# schema_v4_3.net
KiCad netlist of a schematic drawn in EAGLE
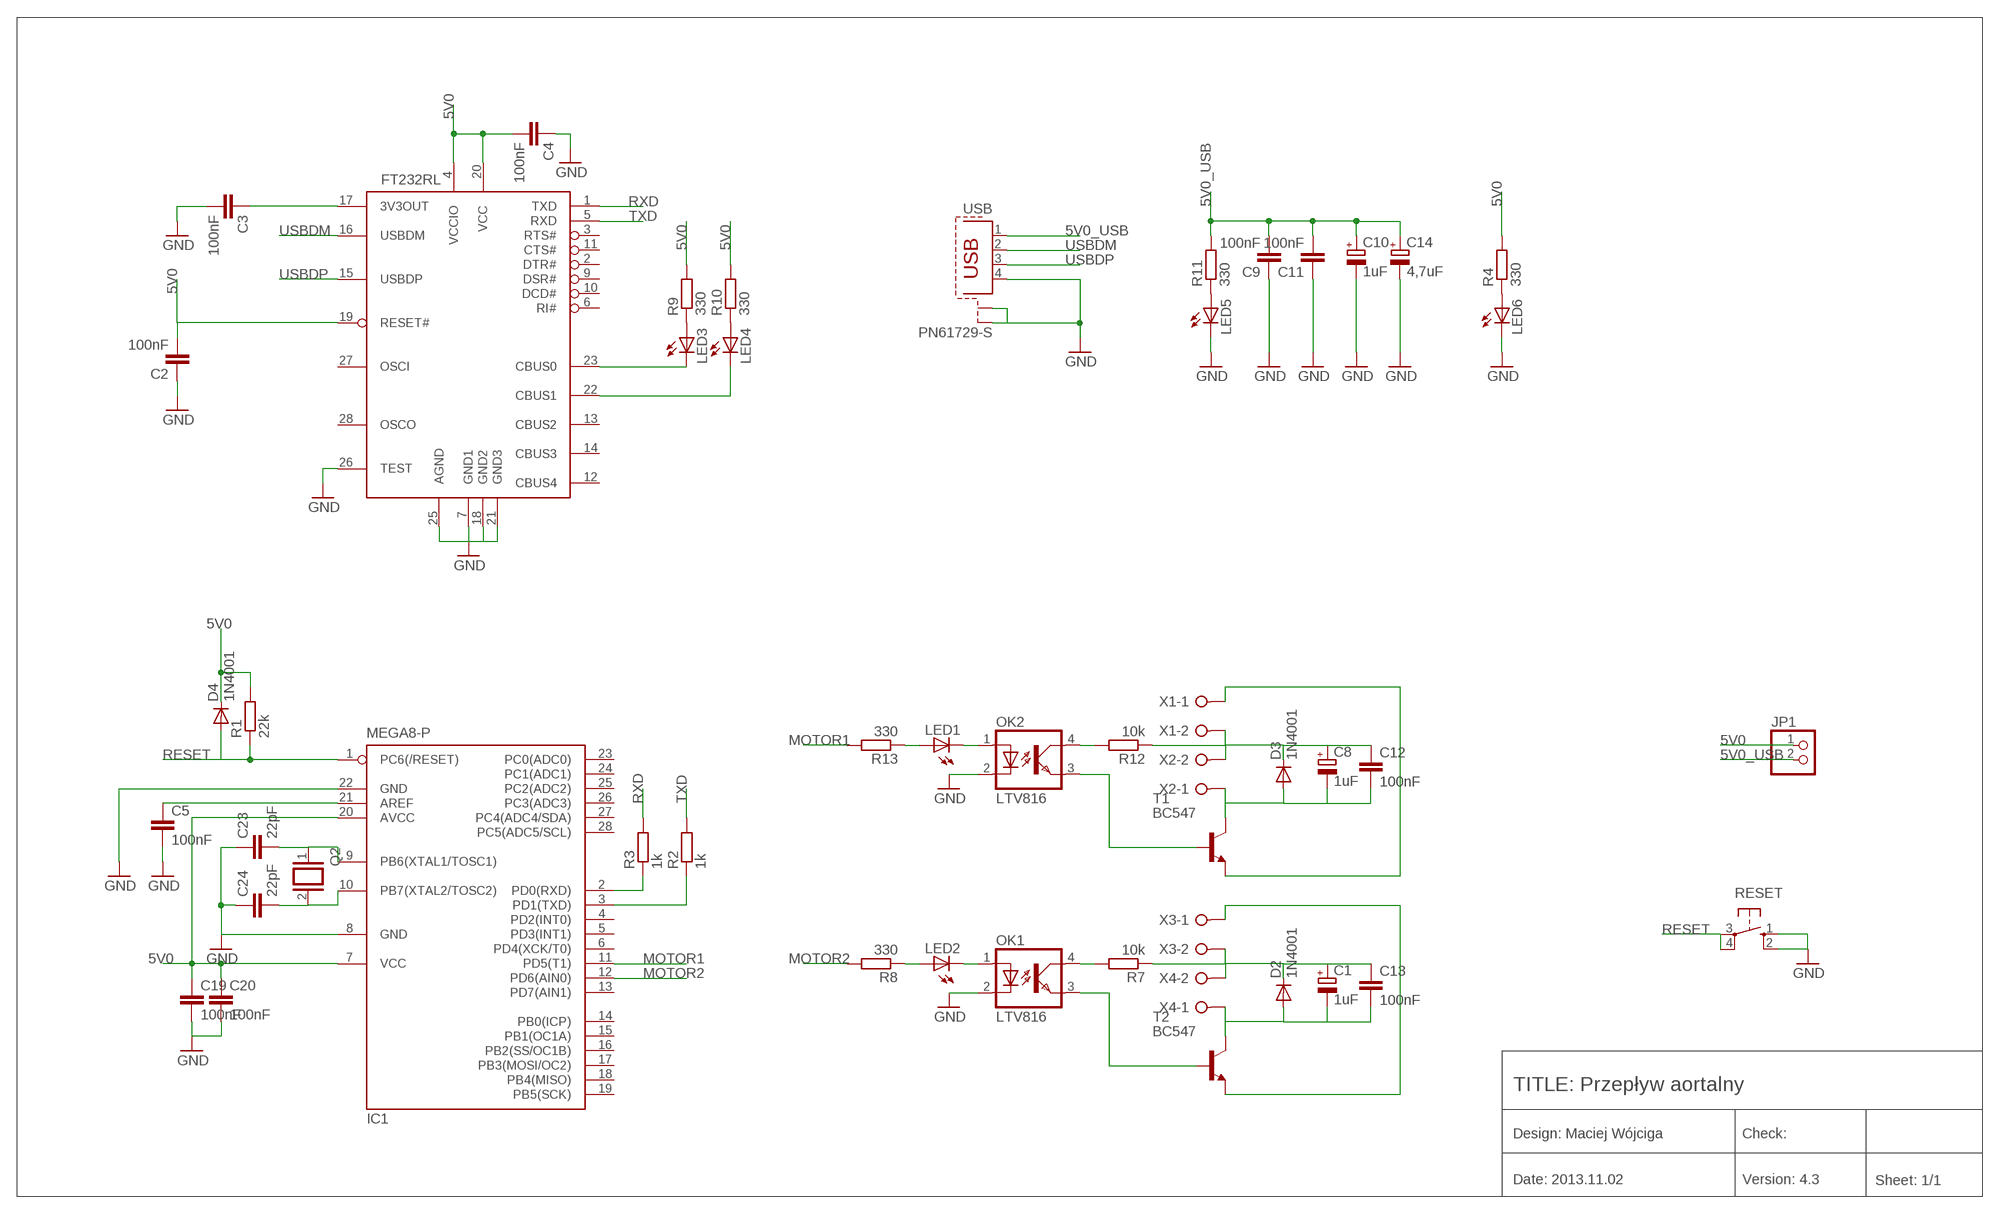
[diagram p0: schematic, sheet 1]

(export (version "E")
  (design (tool "Eeschema 10.0.6"))
  (components
    (comp (ref "C1")
      (value "1uF")
      (footprint "eagle-import:E2,5-5")
      (libsource (lib "eagle-import") (part "CPOL-EUE2.5-5"))
    )
    (comp (ref "C2")
      (value "100nF")
      (footprint "eagle-import:C025-025X050")
      (libsource (lib "eagle-import") (part "C-EU025-025X050"))
    )
    (comp (ref "C3")
      (value "100nF")
      (footprint "eagle-import:C025-025X050")
      (libsource (lib "eagle-import") (part "C-EU025-025X050"))
    )
    (comp (ref "C4")
      (value "100nF")
      (footprint "eagle-import:C025-025X050")
      (libsource (lib "eagle-import") (part "C-EU025-025X050"))
    )
    (comp (ref "C5")
      (value "100nF")
      (footprint "eagle-import:C025-025X050")
      (libsource (lib "eagle-import") (part "C-EU025-025X050"))
    )
    (comp (ref "C8")
      (value "1uF")
      (footprint "eagle-import:E2,5-5")
      (libsource (lib "eagle-import") (part "CPOL-EUE2.5-5"))
    )
    (comp (ref "C9")
      (value "100nF")
      (footprint "eagle-import:C025-025X050")
      (libsource (lib "eagle-import") (part "C-EU025-025X050"))
    )
    (comp (ref "C10")
      (value "1uF")
      (footprint "eagle-import:E2,5-5")
      (libsource (lib "eagle-import") (part "CPOL-EUE2.5-5"))
    )
    (comp (ref "C11")
      (value "100nF")
      (footprint "eagle-import:C025-025X050")
      (libsource (lib "eagle-import") (part "C-EU025-025X050"))
    )
    (comp (ref "C12")
      (value "100nF")
      (footprint "eagle-import:C025-025X050")
      (libsource (lib "eagle-import") (part "C-EU025-025X050"))
    )
    (comp (ref "C13")
      (value "100nF")
      (footprint "eagle-import:C025-025X050")
      (libsource (lib "eagle-import") (part "C-EU025-025X050"))
    )
    (comp (ref "C14")
      (value "4,7uF")
      (footprint "eagle-import:E2,5-5")
      (libsource (lib "eagle-import") (part "CPOL-EUE2.5-5"))
    )
    (comp (ref "C19")
      (value "100nF")
      (footprint "eagle-import:C025-025X050")
      (libsource (lib "eagle-import") (part "C-EU025-025X050"))
    )
    (comp (ref "C20")
      (value "100nF")
      (footprint "eagle-import:C025-025X050")
      (libsource (lib "eagle-import") (part "C-EU025-025X050"))
    )
    (comp (ref "C23")
      (value "22pF")
      (footprint "eagle-import:C025-025X050")
      (libsource (lib "eagle-import") (part "C-EU025-025X050"))
    )
    (comp (ref "C24")
      (value "22pF")
      (footprint "eagle-import:C025-025X050")
      (libsource (lib "eagle-import") (part "C-EU025-025X050"))
    )
    (comp (ref "D2")
      (value "1N4001")
      (footprint "eagle-import:DO41-10")
      (libsource (lib "eagle-import") (part "1N4004"))
    )
    (comp (ref "D3")
      (value "1N4001")
      (footprint "eagle-import:DO41-10")
      (libsource (lib "eagle-import") (part "1N4004"))
    )
    (comp (ref "D4")
      (value "1N4001")
      (footprint "eagle-import:DO41-10")
      (libsource (lib "eagle-import") (part "1N4004"))
    )
    (comp (ref "FT232RL")
      (value "FT232RL")
      (footprint "eagle-import:SSOP28DB")
      (libsource (lib "eagle-import") (part "FT232RL"))
    )
    (comp (ref "IC1")
      (value "MEGA8-P")
      (footprint "eagle-import:DIL28-3")
      (libsource (lib "eagle-import") (part "MEGA8-P"))
    )
    (comp (ref "JP1")
      (value "PINHD-1X2")
      (footprint "eagle-import:1X02")
      (libsource (lib "eagle-import") (part "PINHD-1X2"))
    )
    (comp (ref "LED1")
      (value "LED3MM")
      (footprint "eagle-import:LED3MM")
      (libsource (lib "eagle-import") (part "LED3MM"))
    )
    (comp (ref "LED2")
      (value "LED3MM")
      (footprint "eagle-import:LED3MM")
      (libsource (lib "eagle-import") (part "LED3MM"))
    )
    (comp (ref "LED3")
      (value "LED3MM")
      (footprint "eagle-import:LED3MM")
      (libsource (lib "eagle-import") (part "LED3MM"))
    )
    (comp (ref "LED4")
      (value "LED3MM")
      (footprint "eagle-import:LED3MM")
      (libsource (lib "eagle-import") (part "LED3MM"))
    )
    (comp (ref "LED5")
      (value "LED3MM")
      (footprint "eagle-import:LED3MM")
      (libsource (lib "eagle-import") (part "LED3MM"))
    )
    (comp (ref "LED6")
      (value "LED3MM")
      (footprint "eagle-import:LED3MM")
      (libsource (lib "eagle-import") (part "LED3MM"))
    )
    (comp (ref "OK1")
      (value "LTV816")
      (footprint "eagle-import:DIL04")
      (libsource (lib "eagle-import") (part "LTV816"))
    )
    (comp (ref "OK2")
      (value "LTV816")
      (footprint "eagle-import:DIL04")
      (libsource (lib "eagle-import") (part "LTV816"))
    )
    (comp (ref "Q2")
      (value "XTAL/S")
      (footprint "eagle-import:QS")
      (libsource (lib "eagle-import") (part "XTAL/S"))
    )
    (comp (ref "R1")
      (value "22k")
      (footprint "eagle-import:0207_10")
      (libsource (lib "eagle-import") (part "R-EU_0207/10"))
    )
    (comp (ref "R2")
      (value "1k")
      (footprint "eagle-import:0207_10")
      (libsource (lib "eagle-import") (part "R-EU_0207/10"))
    )
    (comp (ref "R3")
      (value "1k")
      (footprint "eagle-import:0207_10")
      (libsource (lib "eagle-import") (part "R-EU_0207/10"))
    )
    (comp (ref "R4")
      (value "330")
      (footprint "eagle-import:0207_10")
      (libsource (lib "eagle-import") (part "R-EU_0207/10"))
    )
    (comp (ref "R7")
      (value "10k")
      (footprint "eagle-import:0207_10")
      (libsource (lib "eagle-import") (part "R-EU_0207/10"))
    )
    (comp (ref "R8")
      (value "330")
      (footprint "eagle-import:0207_10")
      (libsource (lib "eagle-import") (part "R-EU_0207/10"))
    )
    (comp (ref "R9")
      (value "330")
      (footprint "eagle-import:0207_10")
      (libsource (lib "eagle-import") (part "R-EU_0207/10"))
    )
    (comp (ref "R10")
      (value "330")
      (footprint "eagle-import:0207_10")
      (libsource (lib "eagle-import") (part "R-EU_0207/10"))
    )
    (comp (ref "R11")
      (value "330")
      (footprint "eagle-import:0207_10")
      (libsource (lib "eagle-import") (part "R-EU_0207/10"))
    )
    (comp (ref "R12")
      (value "10k")
      (footprint "eagle-import:0207_10")
      (libsource (lib "eagle-import") (part "R-EU_0207/10"))
    )
    (comp (ref "R13")
      (value "330")
      (footprint "eagle-import:0207_10")
      (libsource (lib "eagle-import") (part "R-EU_0207/10"))
    )
    (comp (ref "RESET")
      (value "10-XX")
      (footprint "eagle-import:B3F-10XX")
      (fields (field (name "MPN") "B3F-1000"))
      (libsource (lib "eagle-import") (part "10-XX"))
    )
    (comp (ref "T1")
      (value "BC547")
      (footprint "eagle-import:TO92")
      (libsource (lib "eagle-import") (part "BC547"))
    )
    (comp (ref "T2")
      (value "BC547")
      (footprint "eagle-import:TO92")
      (libsource (lib "eagle-import") (part "BC547"))
    )
    (comp (ref "USB")
      (value "PN61729-S")
      (footprint "eagle-import:PN61729-S")
      (fields (field (name "OC_FARNELL") "unknown") (field (name "OC_NEWARK") "unknown"))
      (libsource (lib "eagle-import") (part "PN61729-S"))
    )
    (comp (ref "X1")
      (value "W237-02P")
      (footprint "eagle-import:W237-132")
      (fields (field (name "OC_FARNELL") "unknown") (field (name "OC_NEWARK") "unknown"))
      (libsource (lib "eagle-import") (part "W237-02P"))
    )
    (comp (ref "X2")
      (value "W237-02P")
      (footprint "eagle-import:W237-132")
      (fields (field (name "OC_FARNELL") "unknown") (field (name "OC_NEWARK") "unknown"))
      (libsource (lib "eagle-import") (part "W237-02P"))
    )
    (comp (ref "X3")
      (value "W237-02P")
      (footprint "eagle-import:W237-132")
      (fields (field (name "OC_FARNELL") "unknown") (field (name "OC_NEWARK") "unknown"))
      (libsource (lib "eagle-import") (part "W237-02P"))
    )
    (comp (ref "X4")
      (value "W237-02P")
      (footprint "eagle-import:W237-132")
      (fields (field (name "OC_FARNELL") "unknown") (field (name "OC_NEWARK") "unknown"))
      (libsource (lib "eagle-import") (part "W237-02P"))
    )
  )
  (nets
    (net (code "1") (name "/5V0") (class "Default")
      (node (ref "C19") (pin "1") (pinfunction "1_1") (pintype "passive"))
      (node (ref "C2") (pin "2") (pinfunction "2_2") (pintype "passive"))
      (node (ref "C20") (pin "1") (pinfunction "1_1") (pintype "passive"))
      (node (ref "C4") (pin "2") (pinfunction "2_2") (pintype "passive"))
      (node (ref "D4") (pin "C") (pinfunction "C_C") (pintype "passive"))
      (node (ref "FT232RL") (pin "19") (pinfunction "RESET#_19") (pintype "input"))
      (node (ref "FT232RL") (pin "20") (pinfunction "VCC_20") (pintype "power_in"))
      (node (ref "FT232RL") (pin "4") (pinfunction "VCCIO_4") (pintype "power_in"))
      (node (ref "IC1") (pin "20") (pinfunction "AVCC_20") (pintype "power_in"))
      (node (ref "IC1") (pin "7") (pinfunction "VCC_7") (pintype "power_in"))
      (node (ref "JP1") (pin "1") (pinfunction "1_1") (pintype "passive"))
      (node (ref "R1") (pin "2") (pinfunction "2_2") (pintype "passive"))
      (node (ref "R10") (pin "2") (pinfunction "2_2") (pintype "passive"))
      (node (ref "R4") (pin "2") (pinfunction "2_2") (pintype "passive"))
      (node (ref "R9") (pin "2") (pinfunction "2_2") (pintype "passive"))
    )
    (net (code "2") (name "/5V0_USB") (class "Default")
      (node (ref "C10") (pin "+") (pinfunction "+_+") (pintype "passive"))
      (node (ref "C11") (pin "2") (pinfunction "2_2") (pintype "passive"))
      (node (ref "C14") (pin "+") (pinfunction "+_+") (pintype "passive"))
      (node (ref "C9") (pin "2") (pinfunction "2_2") (pintype "passive"))
      (node (ref "JP1") (pin "2") (pinfunction "2_2") (pintype "passive"))
      (node (ref "R11") (pin "2") (pinfunction "2_2") (pintype "passive"))
      (node (ref "USB") (pin "1") (pinfunction "1_1") (pintype "passive"))
    )
    (net (code "3") (name "/MOTOR1") (class "Default")
      (node (ref "IC1") (pin "11") (pinfunction "PD5(T1)_11") (pintype "bidirectional"))
      (node (ref "R13") (pin "2") (pinfunction "2_2") (pintype "passive"))
    )
    (net (code "4") (name "/MOTOR2") (class "Default")
      (node (ref "IC1") (pin "12") (pinfunction "PD6(AIN0)_12") (pintype "bidirectional"))
      (node (ref "R8") (pin "2") (pinfunction "2_2") (pintype "passive"))
    )
    (net (code "5") (name "/RESET") (class "Default")
      (node (ref "D4") (pin "A") (pinfunction "A_A") (pintype "passive"))
      (node (ref "IC1") (pin "1") (pinfunction "PC6(/RESET)_1") (pintype "bidirectional"))
      (node (ref "R1") (pin "1") (pinfunction "1_1") (pintype "passive"))
      (node (ref "RESET") (pin "3") (pinfunction "P_3") (pintype "passive"))
      (node (ref "RESET") (pin "4") (pinfunction "P1_4") (pintype "passive"))
    )
    (net (code "6") (name "/RXD") (class "Default")
      (node (ref "FT232RL") (pin "1") (pinfunction "TXD_1") (pintype "output"))
      (node (ref "R3") (pin "2") (pinfunction "2_2") (pintype "passive"))
    )
    (net (code "7") (name "/TXD") (class "Default")
      (node (ref "FT232RL") (pin "5") (pinfunction "RXD_5") (pintype "input"))
      (node (ref "R2") (pin "2") (pinfunction "2_2") (pintype "passive"))
    )
    (net (code "8") (name "/USBDM") (class "Default")
      (node (ref "FT232RL") (pin "16") (pinfunction "USBDM_16") (pintype "bidirectional"))
      (node (ref "USB") (pin "2") (pinfunction "2_2") (pintype "passive"))
    )
    (net (code "9") (name "/USBDP") (class "Default")
      (node (ref "FT232RL") (pin "15") (pinfunction "USBDP_15") (pintype "bidirectional"))
      (node (ref "USB") (pin "3") (pinfunction "3_3") (pintype "passive"))
    )
    (net (code "10") (name "GND") (class "Default")
      (node (ref "C10") (pin "-") (pinfunction "-_-") (pintype "passive"))
      (node (ref "C11") (pin "1") (pinfunction "1_1") (pintype "passive"))
      (node (ref "C14") (pin "-") (pinfunction "-_-") (pintype "passive"))
      (node (ref "C19") (pin "2") (pinfunction "2_2") (pintype "passive"))
      (node (ref "C2") (pin "1") (pinfunction "1_1") (pintype "passive"))
      (node (ref "C20") (pin "2") (pinfunction "2_2") (pintype "passive"))
      (node (ref "C23") (pin "1") (pinfunction "1_1") (pintype "passive"))
      (node (ref "C24") (pin "1") (pinfunction "1_1") (pintype "passive"))
      (node (ref "C3") (pin "2") (pinfunction "2_2") (pintype "passive"))
      (node (ref "C4") (pin "1") (pinfunction "1_1") (pintype "passive"))
      (node (ref "C5") (pin "2") (pinfunction "2_2") (pintype "passive"))
      (node (ref "C9") (pin "1") (pinfunction "1_1") (pintype "passive"))
      (node (ref "FT232RL") (pin "18") (pinfunction "GND2_18") (pintype "power_in"))
      (node (ref "FT232RL") (pin "21") (pinfunction "GND3_21") (pintype "power_in"))
      (node (ref "FT232RL") (pin "25") (pinfunction "AGND_25") (pintype "power_in"))
      (node (ref "FT232RL") (pin "26") (pinfunction "TEST_26") (pintype "input"))
      (node (ref "FT232RL") (pin "7") (pinfunction "GND1_7") (pintype "power_in"))
      (node (ref "IC1") (pin "22") (pinfunction "GND_22") (pintype "power_in"))
      (node (ref "IC1") (pin "8") (pinfunction "GND_8") (pintype "power_in"))
      (node (ref "LED5") (pin "K") (pinfunction "C_K") (pintype "passive"))
      (node (ref "LED6") (pin "K") (pinfunction "C_K") (pintype "passive"))
      (node (ref "OK1") (pin "2") (pinfunction "C_2") (pintype "passive"))
      (node (ref "OK2") (pin "2") (pinfunction "C_2") (pintype "passive"))
      (node (ref "RESET") (pin "1") (pinfunction "S_1") (pintype "passive"))
      (node (ref "RESET") (pin "2") (pinfunction "S1_2") (pintype "passive"))
      (node (ref "USB") (pin "4") (pinfunction "4_4") (pintype "passive"))
      (node (ref "USB") (pin "S1") (pinfunction "S1_S1") (pintype "passive"))
      (node (ref "USB") (pin "S2") (pinfunction "S2_S2") (pintype "passive"))
    )
    (net (code "11") (name "Net-(FT232RL-3V3OUT)") (class "Default")
      (node (ref "C3") (pin "1") (pinfunction "1_1") (pintype "passive"))
      (node (ref "FT232RL") (pin "17") (pinfunction "3V3OUT_17") (pintype "output"))
    )
    (net (code "12") (name "Net-(FT232RL-CBUS0)") (class "Default")
      (node (ref "FT232RL") (pin "23") (pinfunction "CBUS0_23") (pintype "bidirectional"))
      (node (ref "LED3") (pin "K") (pinfunction "C_K") (pintype "passive"))
    )
    (net (code "13") (name "Net-(FT232RL-CBUS1)") (class "Default")
      (node (ref "FT232RL") (pin "22") (pinfunction "CBUS1_22") (pintype "bidirectional"))
      (node (ref "LED4") (pin "K") (pinfunction "C_K") (pintype "passive"))
    )
    (net (code "14") (name "Net-(IC1-AREF)") (class "Default")
      (node (ref "C5") (pin "1") (pinfunction "1_1") (pintype "passive"))
      (node (ref "IC1") (pin "21") (pinfunction "AREF_21") (pintype "passive"))
    )
    (net (code "15") (name "Net-(IC1-PB6(XTAL1{slash}TOSC1))") (class "Default")
      (node (ref "C23") (pin "2") (pinfunction "2_2") (pintype "passive"))
      (node (ref "IC1") (pin "9") (pinfunction "PB6(XTAL1/TOSC1)_9") (pintype "bidirectional"))
      (node (ref "Q2") (pin "1") (pinfunction "1_1") (pintype "passive"))
    )
    (net (code "16") (name "Net-(IC1-PB7(XTAL2{slash}TOSC2))") (class "Default")
      (node (ref "C24") (pin "2") (pinfunction "2_2") (pintype "passive"))
      (node (ref "IC1") (pin "10") (pinfunction "PB7(XTAL2/TOSC2)_10") (pintype "bidirectional"))
      (node (ref "Q2") (pin "2") (pinfunction "2_2") (pintype "passive"))
    )
    (net (code "17") (name "Net-(IC1-PD0(RXD))") (class "Default")
      (node (ref "IC1") (pin "2") (pinfunction "PD0(RXD)_2") (pintype "bidirectional"))
      (node (ref "R3") (pin "1") (pinfunction "1_1") (pintype "passive"))
    )
    (net (code "18") (name "Net-(IC1-PD1(TXD))") (class "Default")
      (node (ref "IC1") (pin "3") (pinfunction "PD1(TXD)_3") (pintype "bidirectional"))
      (node (ref "R2") (pin "1") (pinfunction "1_1") (pintype "passive"))
    )
    (net (code "19") (name "Net-(LED1-C)") (class "Default")
      (node (ref "LED1") (pin "K") (pinfunction "C_K") (pintype "passive"))
      (node (ref "OK2") (pin "1") (pinfunction "A_1") (pintype "passive"))
    )
    (net (code "20") (name "Net-(LED1-PadA)") (class "Default")
      (node (ref "LED1") (pin "A") (pinfunction "A_A") (pintype "passive"))
      (node (ref "R13") (pin "1") (pinfunction "1_1") (pintype "passive"))
    )
    (net (code "21") (name "Net-(LED2-C)") (class "Default")
      (node (ref "LED2") (pin "K") (pinfunction "C_K") (pintype "passive"))
      (node (ref "OK1") (pin "1") (pinfunction "A_1") (pintype "passive"))
    )
    (net (code "22") (name "Net-(LED2-PadA)") (class "Default")
      (node (ref "LED2") (pin "A") (pinfunction "A_A") (pintype "passive"))
      (node (ref "R8") (pin "1") (pinfunction "1_1") (pintype "passive"))
    )
    (net (code "23") (name "Net-(LED3-PadA)") (class "Default")
      (node (ref "LED3") (pin "A") (pinfunction "A_A") (pintype "passive"))
      (node (ref "R9") (pin "1") (pinfunction "1_1") (pintype "passive"))
    )
    (net (code "24") (name "Net-(LED4-PadA)") (class "Default")
      (node (ref "LED4") (pin "A") (pinfunction "A_A") (pintype "passive"))
      (node (ref "R10") (pin "1") (pinfunction "1_1") (pintype "passive"))
    )
    (net (code "25") (name "Net-(LED5-PadA)") (class "Default")
      (node (ref "LED5") (pin "A") (pinfunction "A_A") (pintype "passive"))
      (node (ref "R11") (pin "1") (pinfunction "1_1") (pintype "passive"))
    )
    (net (code "26") (name "Net-(LED6-PadA)") (class "Default")
      (node (ref "LED6") (pin "A") (pinfunction "A_A") (pintype "passive"))
      (node (ref "R4") (pin "1") (pinfunction "1_1") (pintype "passive"))
    )
    (net (code "27") (name "Net-(OK1-COL)") (class "Default")
      (node (ref "OK1") (pin "4") (pinfunction "COL_4") (pintype "passive"))
      (node (ref "R7") (pin "2") (pinfunction "2_2") (pintype "passive"))
    )
    (net (code "28") (name "Net-(OK1-EMIT)") (class "Default")
      (node (ref "OK1") (pin "3") (pinfunction "EMIT_3") (pintype "passive"))
      (node (ref "T2") (pin "2") (pinfunction "B_2") (pintype "passive"))
    )
    (net (code "29") (name "Net-(OK2-COL)") (class "Default")
      (node (ref "OK2") (pin "4") (pinfunction "COL_4") (pintype "passive"))
      (node (ref "R12") (pin "2") (pinfunction "2_2") (pintype "passive"))
    )
    (net (code "30") (name "Net-(OK2-EMIT)") (class "Default")
      (node (ref "OK2") (pin "3") (pinfunction "EMIT_3") (pintype "passive"))
      (node (ref "T1") (pin "2") (pinfunction "B_2") (pintype "passive"))
    )
    (net (code "31") (name "Net-(T1-C)") (class "Default")
      (node (ref "C12") (pin "2") (pinfunction "2_2") (pintype "passive"))
      (node (ref "C8") (pin "-") (pinfunction "-_-") (pintype "passive"))
      (node (ref "D3") (pin "A") (pinfunction "A_A") (pintype "passive"))
      (node (ref "T1") (pin "3") (pinfunction "C_3") (pintype "passive"))
      (node (ref "X2") (pin "1") (pinfunction "KL_1") (pintype "passive"))
    )
    (net (code "32") (name "Net-(T1-E)") (class "Default")
      (node (ref "T1") (pin "1") (pinfunction "E_1") (pintype "passive"))
      (node (ref "X1") (pin "1") (pinfunction "KL_1") (pintype "passive"))
    )
    (net (code "33") (name "Net-(T2-C)") (class "Default")
      (node (ref "C1") (pin "-") (pinfunction "-_-") (pintype "passive"))
      (node (ref "C13") (pin "2") (pinfunction "2_2") (pintype "passive"))
      (node (ref "D2") (pin "A") (pinfunction "A_A") (pintype "passive"))
      (node (ref "T2") (pin "3") (pinfunction "C_3") (pintype "passive"))
      (node (ref "X4") (pin "1") (pinfunction "KL_1") (pintype "passive"))
    )
    (net (code "34") (name "Net-(T2-E)") (class "Default")
      (node (ref "T2") (pin "1") (pinfunction "E_1") (pintype "passive"))
      (node (ref "X3") (pin "1") (pinfunction "KL_1") (pintype "passive"))
    )
    (net (code "35") (name "Net-(X1B-KL)") (class "Default")
      (node (ref "C12") (pin "1") (pinfunction "1_1") (pintype "passive"))
      (node (ref "C8") (pin "+") (pinfunction "+_+") (pintype "passive"))
      (node (ref "D3") (pin "C") (pinfunction "C_C") (pintype "passive"))
      (node (ref "R12") (pin "1") (pinfunction "1_1") (pintype "passive"))
      (node (ref "X1") (pin "2") (pinfunction "KL_2") (pintype "passive"))
      (node (ref "X2") (pin "2") (pinfunction "KL_2") (pintype "passive"))
    )
    (net (code "36") (name "Net-(X3B-KL)") (class "Default")
      (node (ref "C1") (pin "+") (pinfunction "+_+") (pintype "passive"))
      (node (ref "C13") (pin "1") (pinfunction "1_1") (pintype "passive"))
      (node (ref "D2") (pin "C") (pinfunction "C_C") (pintype "passive"))
      (node (ref "R7") (pin "1") (pinfunction "1_1") (pintype "passive"))
      (node (ref "X3") (pin "2") (pinfunction "KL_2") (pintype "passive"))
      (node (ref "X4") (pin "2") (pinfunction "KL_2") (pintype "passive"))
    )
    (net (code "37") (name "unconnected-(FT232RL-CBUS2-Pad13)") (class "Default")
      (node (ref "FT232RL") (pin "13") (pinfunction "CBUS2_13") (pintype "bidirectional"))
    )
    (net (code "38") (name "unconnected-(FT232RL-CBUS3-Pad14)") (class "Default")
      (node (ref "FT232RL") (pin "14") (pinfunction "CBUS3_14") (pintype "bidirectional"))
    )
    (net (code "39") (name "unconnected-(FT232RL-CBUS4-Pad12)") (class "Default")
      (node (ref "FT232RL") (pin "12") (pinfunction "CBUS4_12") (pintype "bidirectional"))
    )
    (net (code "40") (name "unconnected-(FT232RL-CTS#-Pad11)") (class "Default")
      (node (ref "FT232RL") (pin "11") (pinfunction "CTS#_11") (pintype "input"))
    )
    (net (code "41") (name "unconnected-(FT232RL-DCD#-Pad10)") (class "Default")
      (node (ref "FT232RL") (pin "10") (pinfunction "DCD#_10") (pintype "input"))
    )
    (net (code "42") (name "unconnected-(FT232RL-DSR#-Pad9)") (class "Default")
      (node (ref "FT232RL") (pin "9") (pinfunction "DSR#_9") (pintype "input"))
    )
    (net (code "43") (name "unconnected-(FT232RL-DTR#-Pad2)") (class "Default")
      (node (ref "FT232RL") (pin "2") (pinfunction "DTR#_2") (pintype "output"))
    )
    (net (code "44") (name "unconnected-(FT232RL-OSCI-Pad27)") (class "Default")
      (node (ref "FT232RL") (pin "27") (pinfunction "OSCI_27") (pintype "input"))
    )
    (net (code "45") (name "unconnected-(FT232RL-OSCO-Pad28)") (class "Default")
      (node (ref "FT232RL") (pin "28") (pinfunction "OSCO_28") (pintype "output"))
    )
    (net (code "46") (name "unconnected-(FT232RL-RI#-Pad6)") (class "Default")
      (node (ref "FT232RL") (pin "6") (pinfunction "RI#_6") (pintype "input"))
    )
    (net (code "47") (name "unconnected-(FT232RL-RTS#-Pad3)") (class "Default")
      (node (ref "FT232RL") (pin "3") (pinfunction "RTS#_3") (pintype "output"))
    )
    (net (code "48") (name "unconnected-(IC1-PB0(ICP)-Pad14)") (class "Default")
      (node (ref "IC1") (pin "14") (pinfunction "PB0(ICP)_14") (pintype "bidirectional"))
    )
    (net (code "49") (name "unconnected-(IC1-PB1(OC1A)-Pad15)") (class "Default")
      (node (ref "IC1") (pin "15") (pinfunction "PB1(OC1A)_15") (pintype "bidirectional"))
    )
    (net (code "50") (name "unconnected-(IC1-PB2(SS{slash}OC1B)-Pad16)") (class "Default")
      (node (ref "IC1") (pin "16") (pinfunction "PB2(SS/OC1B)_16") (pintype "bidirectional"))
    )
    (net (code "51") (name "unconnected-(IC1-PB3(MOSI{slash}OC2)-Pad17)") (class "Default")
      (node (ref "IC1") (pin "17") (pinfunction "PB3(MOSI/OC2)_17") (pintype "bidirectional"))
    )
    (net (code "52") (name "unconnected-(IC1-PB4(MISO)-Pad18)") (class "Default")
      (node (ref "IC1") (pin "18") (pinfunction "PB4(MISO)_18") (pintype "bidirectional"))
    )
    (net (code "53") (name "unconnected-(IC1-PB5(SCK)-Pad19)") (class "Default")
      (node (ref "IC1") (pin "19") (pinfunction "PB5(SCK)_19") (pintype "bidirectional"))
    )
    (net (code "54") (name "unconnected-(IC1-PC0(ADC0)-Pad23)") (class "Default")
      (node (ref "IC1") (pin "23") (pinfunction "PC0(ADC0)_23") (pintype "bidirectional"))
    )
    (net (code "55") (name "unconnected-(IC1-PC1(ADC1)-Pad24)") (class "Default")
      (node (ref "IC1") (pin "24") (pinfunction "PC1(ADC1)_24") (pintype "bidirectional"))
    )
    (net (code "56") (name "unconnected-(IC1-PC2(ADC2)-Pad25)") (class "Default")
      (node (ref "IC1") (pin "25") (pinfunction "PC2(ADC2)_25") (pintype "bidirectional"))
    )
    (net (code "57") (name "unconnected-(IC1-PC3(ADC3)-Pad26)") (class "Default")
      (node (ref "IC1") (pin "26") (pinfunction "PC3(ADC3)_26") (pintype "bidirectional"))
    )
    (net (code "58") (name "unconnected-(IC1-PC4(ADC4{slash}SDA)-Pad27)") (class "Default")
      (node (ref "IC1") (pin "27") (pinfunction "PC4(ADC4/SDA)_27") (pintype "bidirectional"))
    )
    (net (code "59") (name "unconnected-(IC1-PC5(ADC5{slash}SCL)-Pad28)") (class "Default")
      (node (ref "IC1") (pin "28") (pinfunction "PC5(ADC5/SCL)_28") (pintype "bidirectional"))
    )
    (net (code "60") (name "unconnected-(IC1-PD2(INT0)-Pad4)") (class "Default")
      (node (ref "IC1") (pin "4") (pinfunction "PD2(INT0)_4") (pintype "bidirectional"))
    )
    (net (code "61") (name "unconnected-(IC1-PD3(INT1)-Pad5)") (class "Default")
      (node (ref "IC1") (pin "5") (pinfunction "PD3(INT1)_5") (pintype "bidirectional"))
    )
    (net (code "62") (name "unconnected-(IC1-PD4(XCK{slash}T0)-Pad6)") (class "Default")
      (node (ref "IC1") (pin "6") (pinfunction "PD4(XCK/T0)_6") (pintype "bidirectional"))
    )
    (net (code "63") (name "unconnected-(IC1-PD7(AIN1)-Pad13)") (class "Default")
      (node (ref "IC1") (pin "13") (pinfunction "PD7(AIN1)_13") (pintype "bidirectional"))
    )
  )
)
